# design.net
KiCad netlist of a schematic drawn in EasyEDA Pro
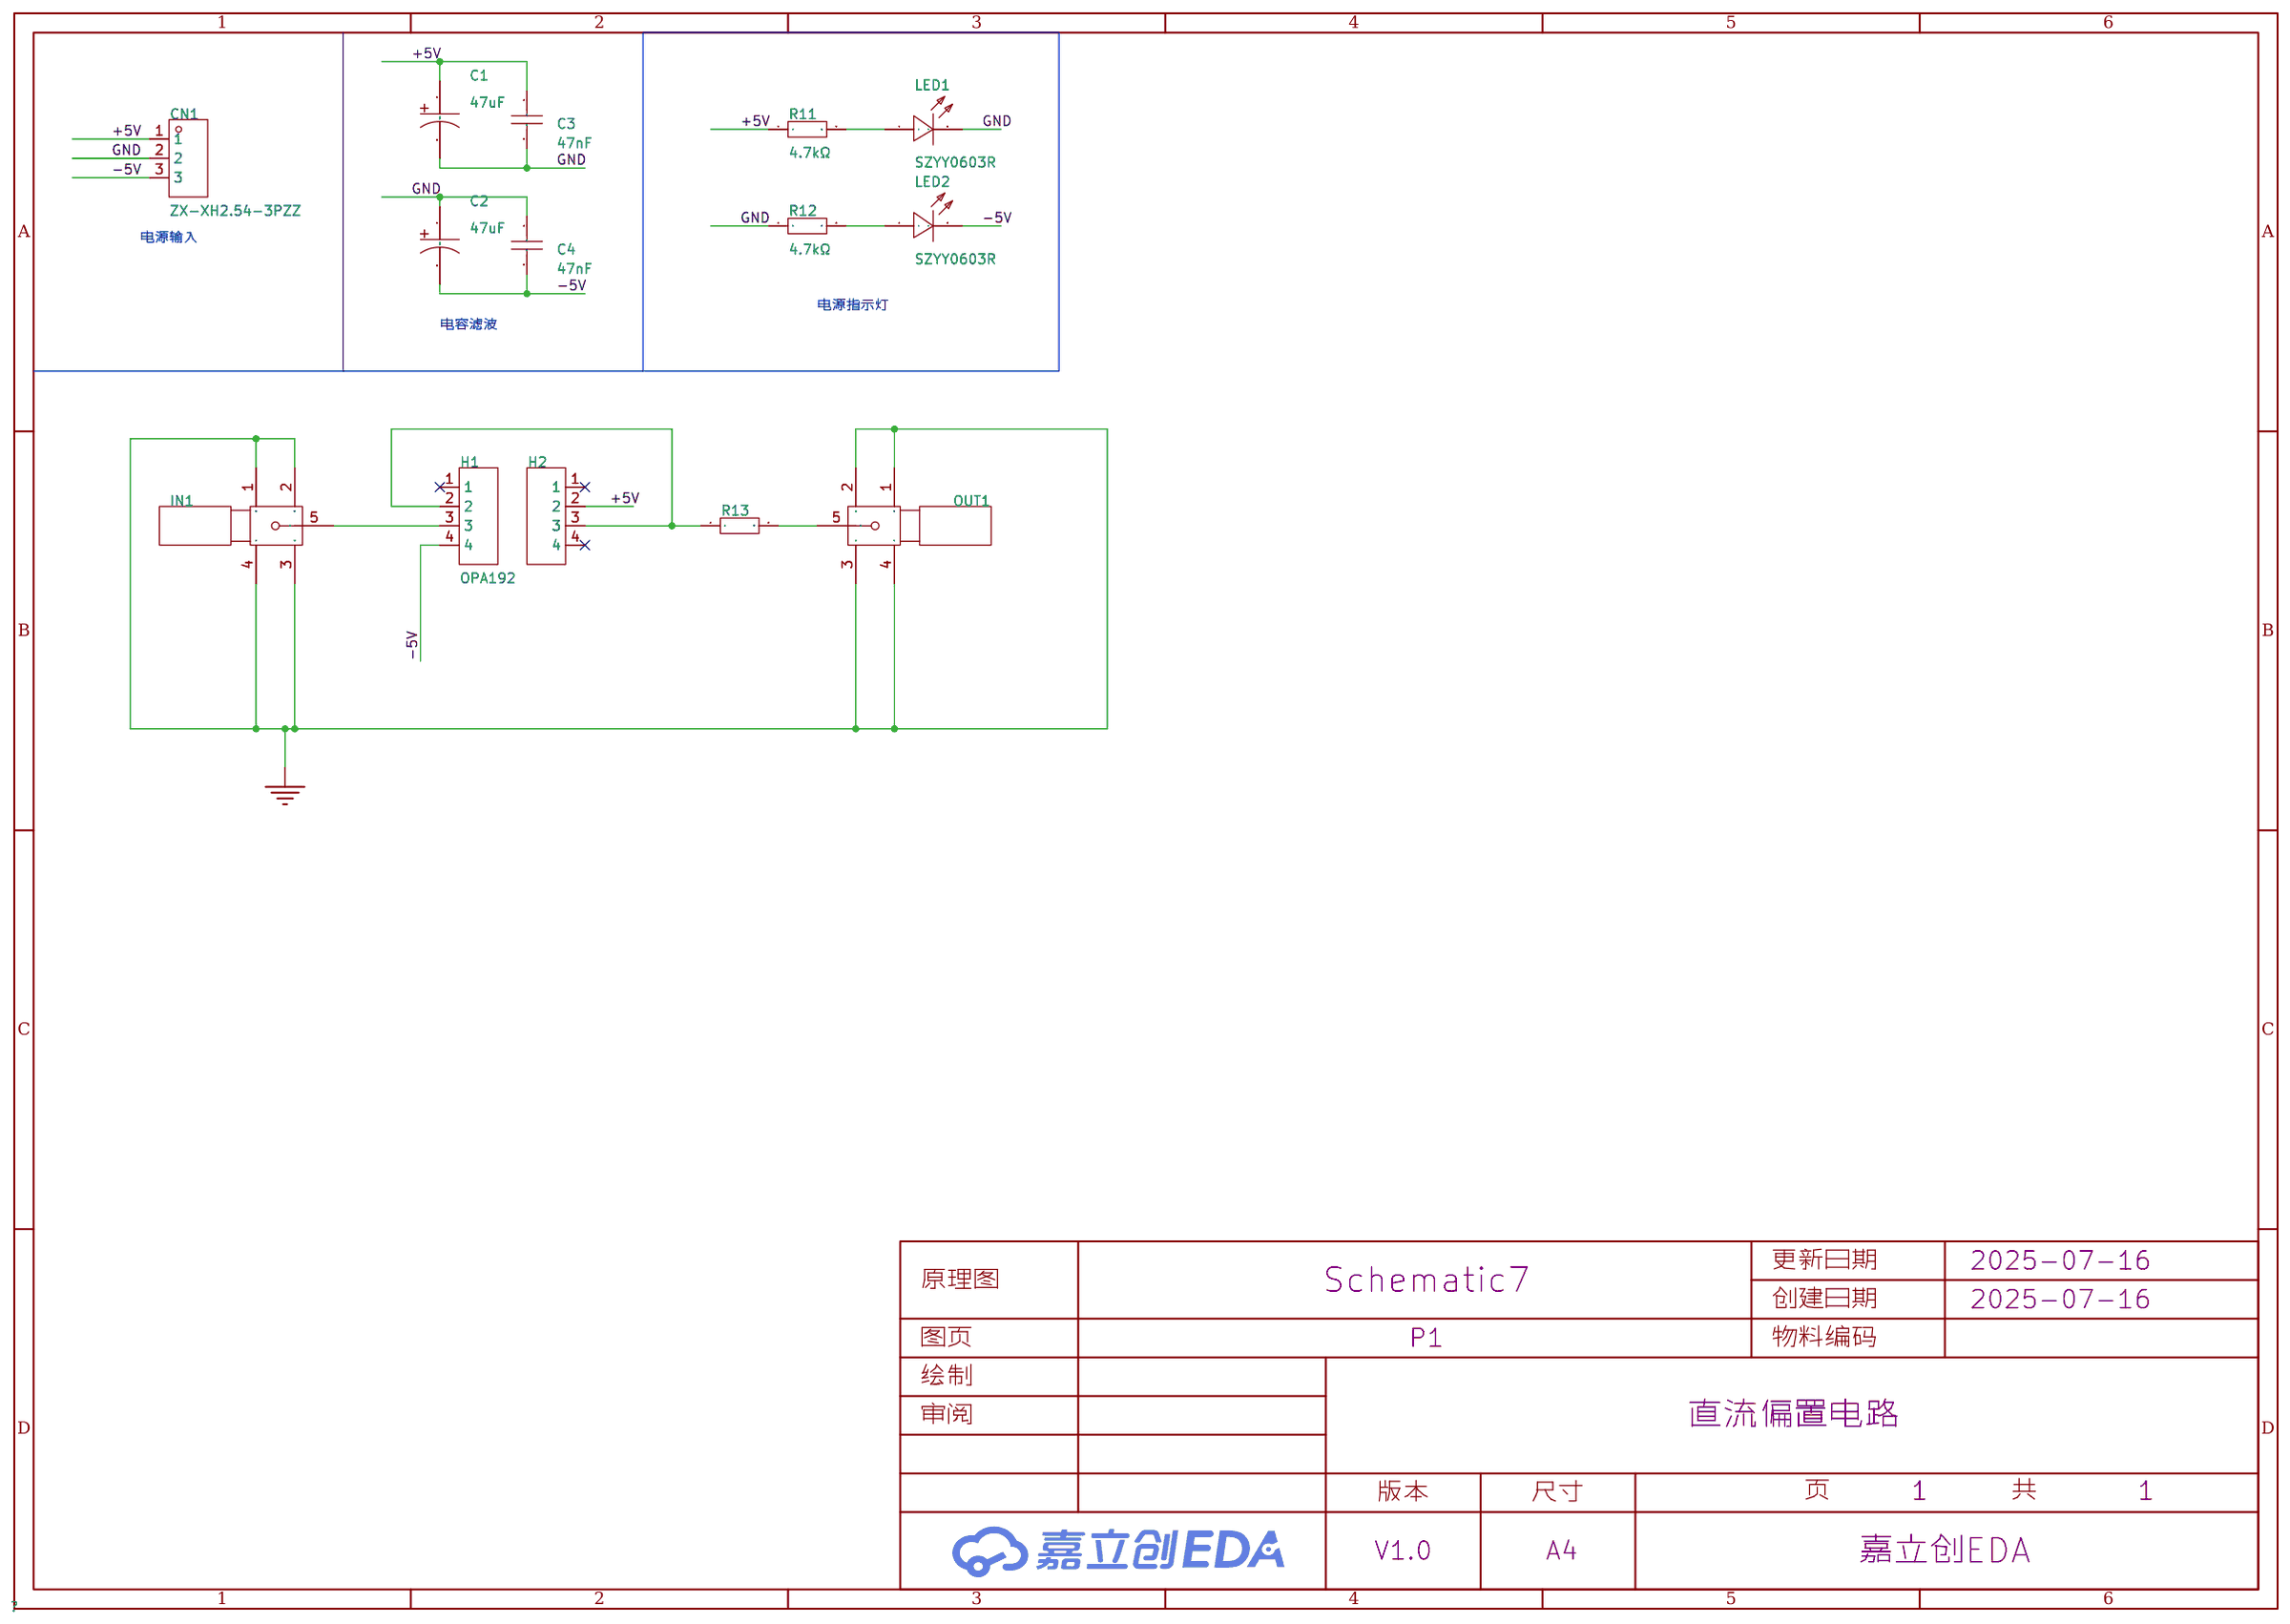
[diagram p0: schematic sheet]

(export (version "E")
  (design (tool "Eeschema 10.0.6"))
  (components
    (comp (ref "C1")
      (value "47uF")
      (footprint "easyedapro:CAP-TH_BD5.0-P2.00-D0.8-FD")
      (description "容值:47uF;精度:±20%;额定电压:25V;纹波电流:250mA@100kHz;等效串联电阻(ESR):300mΩ@100kHz;")
      (fields
        (field (name "Manufacturer Part") "NXB25V47M5*11 2.5TP")
        (field (name "Manufacturer") "SAMYOUNG(韩国三莹)")
      )
      (libsource (lib "easyedapro") (part "NXB25VB47M5*11_2.5TP"))
    )
    (comp (ref "C2")
      (value "47uF")
      (footprint "easyedapro:CAP-TH_BD5.0-P2.00-D0.8-FD")
      (description "容值:47uF;精度:±20%;额定电压:25V;纹波电流:250mA@100kHz;等效串联电阻(ESR):300mΩ@100kHz;")
      (fields
        (field (name "Manufacturer Part") "NXB25V47M5*11 2.5TP")
        (field (name "Manufacturer") "SAMYOUNG(韩国三莹)")
      )
      (libsource (lib "easyedapro") (part "NXB25VB47M5*11_2.5TP"))
    )
    (comp (ref "C3")
      (value "47nF")
      (footprint "easyedapro:C0805")
      (description "容值:47nF;精度:±10%;额定电压:50V;材质(温度系数):X7R;")
      (fields
        (field (name "Manufacturer Part") "CL21B473KBCNNNC")
        (field (name "Manufacturer") "SAMSUNG(三星)")
      )
      (libsource (lib "easyedapro") (part "CL21B473KBCNNNC"))
    )
    (comp (ref "C4")
      (value "47nF")
      (footprint "easyedapro:C0805")
      (description "容值:47nF;精度:±10%;额定电压:50V;材质(温度系数):X7R;")
      (fields
        (field (name "Manufacturer Part") "CL21B473KBCNNNC")
        (field (name "Manufacturer") "SAMSUNG(三星)")
      )
      (libsource (lib "easyedapro") (part "CL21B473KBCNNNC"))
    )
    (comp (ref "CN1")
      (value "ZX-XH2.54-3PZZ")
      (footprint "easyedapro:CONN-TH_3P-P2.54_2501S-3P")
      (fields (field (name "Manufacturer") "Megastar(兆星)"))
      (libsource (lib "easyedapro") (part "ZX-XH2.54-3PZZ"))
    )
    (comp (ref "H1")
      (value "OPA192")
      (footprint "easyedapro:HDR-TH_4P-P2.54-V-F")
      (fields (field (name "Manufacturer") "HC(虹成电子)"))
      (libsource (lib "easyedapro") (part "HC-PM254-5.0H-1X4PZ-02A"))
    )
    (comp (ref "H2")
      (value "HC-PM254-5.0H-1x4PZ-02A")
      (footprint "easyedapro:HDR-TH_4P-P2.54-V-F")
      (fields (field (name "Manufacturer") "HC(虹成电子)"))
      (libsource (lib "easyedapro") (part "HC-PM254-5.0H-1X4PZ-02A"))
    )
    (comp (ref "IN1")
      (value "-")
      (footprint "easyedapro:SMA-SMD_BWSMA-KE-P001")
      (description "连接器类型:板端;接口类型:内孔;端口数量:1;接口直径:5.2mm;接口长度/高度:-;频率:-;射频系列:SMA;阻抗:50Ω;样式:偏脚;工作温度:-;")
      (fields
        (field (name "Manufacturer Part") "BWSMA-KE-P001")
        (field (name "Manufacturer") "BAT WIRELESS(蝙蝠无线)")
      )
      (libsource (lib "easyedapro") (part "BWSMA-KE-P001"))
    )
    (comp (ref "LED1")
      (value "SZYY0603R")
      (footprint "easyedapro:LED0603-R-RD")
      (fields (field (name "Manufacturer") "yongyu(永裕光电)"))
      (libsource (lib "easyedapro") (part "SZYY0603R"))
    )
    (comp (ref "LED2")
      (value "SZYY0603R")
      (footprint "easyedapro:LED0603-R-RD")
      (fields (field (name "Manufacturer") "yongyu(永裕光电)"))
      (libsource (lib "easyedapro") (part "SZYY0603R"))
    )
    (comp (ref "OUT1")
      (value "-")
      (footprint "easyedapro:SMA-SMD_BWSMA-KE-P001")
      (description "连接器类型:板端;接口类型:内孔;端口数量:1;接口直径:5.2mm;接口长度/高度:-;频率:-;射频系列:SMA;阻抗:50Ω;样式:偏脚;工作温度:-;")
      (fields
        (field (name "Manufacturer Part") "BWSMA-KE-P001")
        (field (name "Manufacturer") "BAT WIRELESS(蝙蝠无线)")
      )
      (libsource (lib "easyedapro") (part "BWSMA-KE-P001"))
    )
    (comp (ref "R11")
      (value "4.7kΩ")
      (footprint "easyedapro:R0805")
      (description "电阻类型:厚膜电阻;阻值:4.7kΩ;精度:±1%;功率:125mW;最大工作电压:150V;温度系数:±100ppm/°C;")
      (fields
        (field (name "Manufacturer Part") "0805W8F4701T5E")
        (field (name "Manufacturer") "UNI-ROYAL(厚声)")
      )
      (libsource (lib "easyedapro") (part "0805W8F4701T5E"))
    )
    (comp (ref "R12")
      (value "4.7kΩ")
      (footprint "easyedapro:R0805")
      (description "电阻类型:厚膜电阻;阻值:4.7kΩ;精度:±1%;功率:125mW;最大工作电压:150V;温度系数:±100ppm/°C;")
      (fields
        (field (name "Manufacturer Part") "0805W8F4701T5E")
        (field (name "Manufacturer") "UNI-ROYAL(厚声)")
      )
      (libsource (lib "easyedapro") (part "0805W8F4701T5E"))
    )
    (comp (ref "R13")
      (value "0805W8F200JT5E")
      (footprint "easyedapro:R0805")
      (fields (field (name "Manufacturer") "UNI-ROYAL(厚声)"))
      (libsource (lib "easyedapro") (part "0805W8F200JT5E"))
    )
  )
  (nets
    (net (code "1") (name "/+5V") (class "Default")
      (node (ref "C1") (pin "1") (pinfunction "1_1") (pintype "unspecified"))
      (node (ref "C3") (pin "2") (pinfunction "2_2") (pintype "input"))
      (node (ref "CN1") (pin "1") (pinfunction "1_1") (pintype "unspecified"))
      (node (ref "H2") (pin "2") (pinfunction "2_2") (pintype "unspecified"))
      (node (ref "R11") (pin "1") (pinfunction "1_1") (pintype "input"))
    )
    (net (code "2") (name "/-5V") (class "Default")
      (node (ref "C2") (pin "2") (pinfunction "2_2") (pintype "unspecified"))
      (node (ref "C4") (pin "1") (pinfunction "1_1") (pintype "input"))
      (node (ref "CN1") (pin "3") (pinfunction "3_3") (pintype "unspecified"))
      (node (ref "H1") (pin "4") (pinfunction "4_4") (pintype "unspecified"))
      (node (ref "LED2") (pin "2") (pinfunction "-_2") (pintype "unspecified"))
    )
    (net (code "3") (name "GND") (class "Default")
      (node (ref "C1") (pin "2") (pinfunction "2_2") (pintype "unspecified"))
      (node (ref "C2") (pin "1") (pinfunction "1_1") (pintype "unspecified"))
      (node (ref "C3") (pin "1") (pinfunction "1_1") (pintype "input"))
      (node (ref "C4") (pin "2") (pinfunction "2_2") (pintype "input"))
      (node (ref "CN1") (pin "2") (pinfunction "2_2") (pintype "unspecified"))
      (node (ref "IN1") (pin "1") (pinfunction "1_1") (pintype "unspecified"))
      (node (ref "IN1") (pin "2") (pinfunction "2_2") (pintype "unspecified"))
      (node (ref "IN1") (pin "3") (pinfunction "3_3") (pintype "unspecified"))
      (node (ref "IN1") (pin "4") (pinfunction "4_4") (pintype "unspecified"))
      (node (ref "LED1") (pin "2") (pinfunction "-_2") (pintype "unspecified"))
      (node (ref "OUT1") (pin "1") (pinfunction "1_1") (pintype "unspecified"))
      (node (ref "OUT1") (pin "2") (pinfunction "2_2") (pintype "unspecified"))
      (node (ref "OUT1") (pin "3") (pinfunction "3_3") (pintype "unspecified"))
      (node (ref "OUT1") (pin "4") (pinfunction "4_4") (pintype "unspecified"))
      (node (ref "R12") (pin "1") (pinfunction "1_1") (pintype "input"))
    )
    (net (code "4") (name "Net-(H1-Pad2)") (class "Default")
      (node (ref "H1") (pin "2") (pinfunction "2_2") (pintype "unspecified"))
      (node (ref "H2") (pin "3") (pinfunction "3_3") (pintype "unspecified"))
      (node (ref "R13") (pin "1") (pinfunction "1_1") (pintype "input"))
    )
    (net (code "5") (name "Net-(H1-Pad3)") (class "Default")
      (node (ref "H1") (pin "3") (pinfunction "3_3") (pintype "unspecified"))
      (node (ref "IN1") (pin "5") (pinfunction "5_5") (pintype "unspecified"))
    )
    (net (code "6") (name "Net-(LED1-+)") (class "Default")
      (node (ref "LED1") (pin "1") (pinfunction "+_1") (pintype "unspecified"))
      (node (ref "R11") (pin "2") (pinfunction "2_2") (pintype "input"))
    )
    (net (code "7") (name "Net-(LED2-+)") (class "Default")
      (node (ref "LED2") (pin "1") (pinfunction "+_1") (pintype "unspecified"))
      (node (ref "R12") (pin "2") (pinfunction "2_2") (pintype "input"))
    )
    (net (code "8") (name "Net-(OUT1-Pad5)") (class "Default")
      (node (ref "OUT1") (pin "5") (pinfunction "5_5") (pintype "unspecified"))
      (node (ref "R13") (pin "2") (pinfunction "2_2") (pintype "input"))
    )
    (net (code "9") (name "unconnected-(H1-Pad1)") (class "Default")
      (node (ref "H1") (pin "1") (pinfunction "1_1") (pintype "unspecified+no_connect"))
    )
    (net (code "10") (name "unconnected-(H2-Pad1)") (class "Default")
      (node (ref "H2") (pin "1") (pinfunction "1_1") (pintype "unspecified+no_connect"))
    )
    (net (code "11") (name "unconnected-(H2-Pad4)") (class "Default")
      (node (ref "H2") (pin "4") (pinfunction "4_4") (pintype "unspecified+no_connect"))
    )
  )
)
